# ADC.net
KiCad netlist of a schematic drawn in Altium Designer
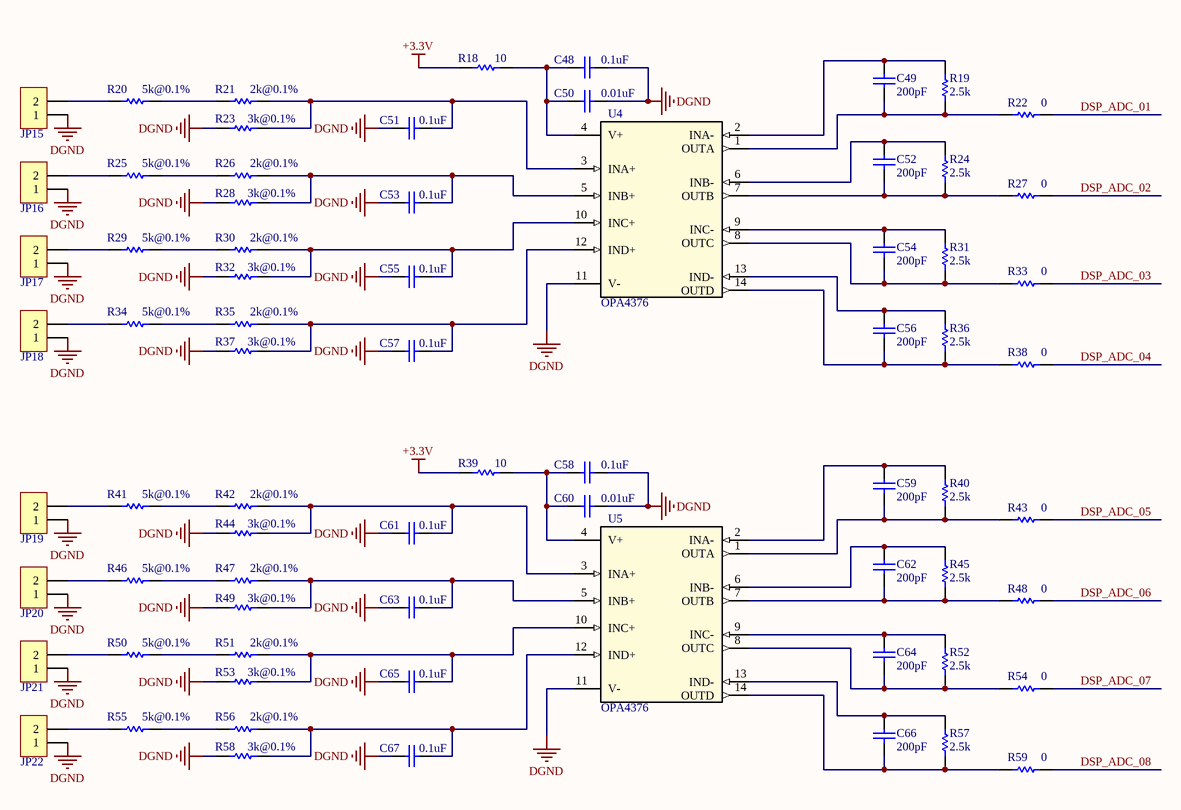
[diagram p0: ADC.SchDoc]

(export (version "E")
  (design (tool "Eeschema 10.0.6"))
  (components
    (comp (ref "C48")
      (value "0.1uF")
      (footprint "1608[0603]")
      (description "Capacitor")
      (fields (field (name "Comment") "Cap") (field (name "PUBLISHER") "Altium Limited"))
      (libsource (lib "Miscellaneous Devices") (part "Cap"))
    )
    (comp (ref "C49")
      (value "200pF")
      (footprint "1608[0603]")
      (description "Capacitor")
      (fields (field (name "Comment") "Cap") (field (name "PUBLISHER") "Altium Limited"))
      (libsource (lib "Miscellaneous Devices") (part "Cap"))
    )
    (comp (ref "C50")
      (value "0.01uF")
      (footprint "1608[0603]")
      (description "Capacitor")
      (fields (field (name "Comment") "Cap") (field (name "PUBLISHER") "Altium Limited"))
      (libsource (lib "Miscellaneous Devices") (part "Cap"))
    )
    (comp (ref "C51")
      (value "0.1uF")
      (footprint "1608[0603]")
      (description "Capacitor")
      (fields (field (name "Comment") "Cap") (field (name "PUBLISHER") "Altium Limited"))
      (libsource (lib "Miscellaneous Devices") (part "Cap"))
    )
    (comp (ref "C52")
      (value "200pF")
      (footprint "1608[0603]")
      (description "Capacitor")
      (fields (field (name "Comment") "Cap") (field (name "PUBLISHER") "Altium Limited"))
      (libsource (lib "Miscellaneous Devices") (part "Cap"))
    )
    (comp (ref "C53")
      (value "0.1uF")
      (footprint "1608[0603]")
      (description "Capacitor")
      (fields (field (name "Comment") "Cap") (field (name "PUBLISHER") "Altium Limited"))
      (libsource (lib "Miscellaneous Devices") (part "Cap"))
    )
    (comp (ref "C54")
      (value "200pF")
      (footprint "1608[0603]")
      (description "Capacitor")
      (fields (field (name "Comment") "Cap") (field (name "PUBLISHER") "Altium Limited"))
      (libsource (lib "Miscellaneous Devices") (part "Cap"))
    )
    (comp (ref "C55")
      (value "0.1uF")
      (footprint "1608[0603]")
      (description "Capacitor")
      (fields (field (name "Comment") "Cap") (field (name "PUBLISHER") "Altium Limited"))
      (libsource (lib "Miscellaneous Devices") (part "Cap"))
    )
    (comp (ref "C56")
      (value "200pF")
      (footprint "1608[0603]")
      (description "Capacitor")
      (fields (field (name "Comment") "Cap") (field (name "PUBLISHER") "Altium Limited"))
      (libsource (lib "Miscellaneous Devices") (part "Cap"))
    )
    (comp (ref "C57")
      (value "0.1uF")
      (footprint "1608[0603]")
      (description "Capacitor")
      (fields (field (name "Comment") "Cap") (field (name "PUBLISHER") "Altium Limited"))
      (libsource (lib "Miscellaneous Devices") (part "Cap"))
    )
    (comp (ref "C58")
      (value "0.1uF")
      (footprint "1608[0603]")
      (description "Capacitor")
      (fields (field (name "Comment") "Cap") (field (name "PUBLISHER") "Altium Limited"))
      (libsource (lib "Miscellaneous Devices") (part "Cap"))
    )
    (comp (ref "C59")
      (value "200pF")
      (footprint "1608[0603]")
      (description "Capacitor")
      (fields (field (name "Comment") "Cap") (field (name "PUBLISHER") "Altium Limited"))
      (libsource (lib "Miscellaneous Devices") (part "Cap"))
    )
    (comp (ref "C60")
      (value "0.01uF")
      (footprint "1608[0603]")
      (description "Capacitor")
      (fields (field (name "Comment") "Cap") (field (name "PUBLISHER") "Altium Limited"))
      (libsource (lib "Miscellaneous Devices") (part "Cap"))
    )
    (comp (ref "C61")
      (value "0.1uF")
      (footprint "1608[0603]")
      (description "Capacitor")
      (fields (field (name "Comment") "Cap") (field (name "PUBLISHER") "Altium Limited"))
      (libsource (lib "Miscellaneous Devices") (part "Cap"))
    )
    (comp (ref "C62")
      (value "200pF")
      (footprint "1608[0603]")
      (description "Capacitor")
      (fields (field (name "Comment") "Cap") (field (name "PUBLISHER") "Altium Limited"))
      (libsource (lib "Miscellaneous Devices") (part "Cap"))
    )
    (comp (ref "C63")
      (value "0.1uF")
      (footprint "1608[0603]")
      (description "Capacitor")
      (fields (field (name "Comment") "Cap") (field (name "PUBLISHER") "Altium Limited"))
      (libsource (lib "Miscellaneous Devices") (part "Cap"))
    )
    (comp (ref "C64")
      (value "200pF")
      (footprint "1608[0603]")
      (description "Capacitor")
      (fields (field (name "Comment") "Cap") (field (name "PUBLISHER") "Altium Limited"))
      (libsource (lib "Miscellaneous Devices") (part "Cap"))
    )
    (comp (ref "C65")
      (value "0.1uF")
      (footprint "1608[0603]")
      (description "Capacitor")
      (fields (field (name "Comment") "Cap") (field (name "PUBLISHER") "Altium Limited"))
      (libsource (lib "Miscellaneous Devices") (part "Cap"))
    )
    (comp (ref "C66")
      (value "200pF")
      (footprint "1608[0603]")
      (description "Capacitor")
      (fields (field (name "Comment") "Cap") (field (name "PUBLISHER") "Altium Limited"))
      (libsource (lib "Miscellaneous Devices") (part "Cap"))
    )
    (comp (ref "C67")
      (value "0.1uF")
      (footprint "1608[0603]")
      (description "Capacitor")
      (fields (field (name "Comment") "Cap") (field (name "PUBLISHER") "Altium Limited"))
      (libsource (lib "Miscellaneous Devices") (part "Cap"))
    )
    (comp (ref "JP15")
      (value "HDR-1X2")
      (footprint "MX 1.25-WI-2P")
      (description "2P接插件")
      (fields (field (name "版权归属") "源创客"))
      (libsource (lib "4.2   - 接插件-脚距1.25") (part "Header 2"))
    )
    (comp (ref "JP16")
      (value "HDR-1X2")
      (footprint "MX 1.25-WI-2P")
      (description "2P接插件")
      (fields (field (name "版权归属") "源创客"))
      (libsource (lib "4.2   - 接插件-脚距1.25") (part "Header 2"))
    )
    (comp (ref "JP17")
      (value "HDR-1X2")
      (footprint "MX 1.25-WI-2P")
      (description "2P接插件")
      (fields (field (name "版权归属") "源创客"))
      (libsource (lib "4.2   - 接插件-脚距1.25") (part "Header 2"))
    )
    (comp (ref "JP18")
      (value "HDR-1X2")
      (footprint "MX 1.25-WI-2P")
      (description "2P接插件")
      (fields (field (name "版权归属") "源创客"))
      (libsource (lib "4.2   - 接插件-脚距1.25") (part "Header 2"))
    )
    (comp (ref "JP19")
      (value "HDR-1X2")
      (footprint "MX 1.25-WI-2P")
      (description "2P接插件")
      (fields (field (name "版权归属") "源创客"))
      (libsource (lib "4.2   - 接插件-脚距1.25") (part "Header 2"))
    )
    (comp (ref "JP20")
      (value "HDR-1X2")
      (footprint "MX 1.25-WI-2P")
      (description "2P接插件")
      (fields (field (name "版权归属") "源创客"))
      (libsource (lib "4.2   - 接插件-脚距1.25") (part "Header 2"))
    )
    (comp (ref "JP21")
      (value "HDR-1X2")
      (footprint "MX 1.25-WI-2P")
      (description "2P接插件")
      (fields (field (name "版权归属") "源创客"))
      (libsource (lib "4.2   - 接插件-脚距1.25") (part "Header 2"))
    )
    (comp (ref "JP22")
      (value "HDR-1X2")
      (footprint "MX 1.25-WI-2P")
      (description "2P接插件")
      (fields (field (name "版权归属") "源创客"))
      (libsource (lib "4.2   - 接插件-脚距1.25") (part "Header 2"))
    )
    (comp (ref "R18")
      (value "10")
      (footprint "1608[0603]")
      (description "Resistor")
      (fields (field (name "Comment") "Res1") (field (name "PUBLISHER") "Altium Limited"))
      (libsource (lib "Miscellaneous Devices") (part "Res1"))
    )
    (comp (ref "R19")
      (value "2.5k")
      (footprint "1608[0603]")
      (description "Resistor")
      (fields (field (name "Comment") "Res1") (field (name "PUBLISHER") "Altium Limited"))
      (libsource (lib "Miscellaneous Devices") (part "Res1"))
    )
    (comp (ref "R20")
      (value "5k@0.1%")
      (footprint "1608[0603]")
      (description "Resistor")
      (fields (field (name "Comment") "Res1") (field (name "PUBLISHER") "Altium Limited"))
      (libsource (lib "Miscellaneous Devices") (part "Res1"))
    )
    (comp (ref "R21")
      (value "2k@0.1%")
      (footprint "1608[0603]")
      (description "Resistor")
      (fields (field (name "Comment") "Res1") (field (name "PUBLISHER") "Altium Limited"))
      (libsource (lib "Miscellaneous Devices") (part "Res1"))
    )
    (comp (ref "R22")
      (value "0")
      (footprint "1608[0603]")
      (description "Resistor")
      (fields (field (name "Comment") "Res1") (field (name "PUBLISHER") "Altium Limited"))
      (libsource (lib "Miscellaneous Devices") (part "Res1"))
    )
    (comp (ref "R23")
      (value "3k@0.1%")
      (footprint "1608[0603]")
      (description "Resistor")
      (fields (field (name "Comment") "Res1") (field (name "PUBLISHER") "Altium Limited"))
      (libsource (lib "Miscellaneous Devices") (part "Res1"))
    )
    (comp (ref "R24")
      (value "2.5k")
      (footprint "1608[0603]")
      (description "Resistor")
      (fields (field (name "Comment") "Res1") (field (name "PUBLISHER") "Altium Limited"))
      (libsource (lib "Miscellaneous Devices") (part "Res1"))
    )
    (comp (ref "R25")
      (value "5k@0.1%")
      (footprint "1608[0603]")
      (description "Resistor")
      (fields (field (name "Comment") "Res1") (field (name "PUBLISHER") "Altium Limited"))
      (libsource (lib "Miscellaneous Devices") (part "Res1"))
    )
    (comp (ref "R26")
      (value "2k@0.1%")
      (footprint "1608[0603]")
      (description "Resistor")
      (fields (field (name "Comment") "Res1") (field (name "PUBLISHER") "Altium Limited"))
      (libsource (lib "Miscellaneous Devices") (part "Res1"))
    )
    (comp (ref "R27")
      (value "0")
      (footprint "1608[0603]")
      (description "Resistor")
      (fields (field (name "Comment") "Res1") (field (name "PUBLISHER") "Altium Limited"))
      (libsource (lib "Miscellaneous Devices") (part "Res1"))
    )
    (comp (ref "R28")
      (value "3k@0.1%")
      (footprint "1608[0603]")
      (description "Resistor")
      (fields (field (name "Comment") "Res1") (field (name "PUBLISHER") "Altium Limited"))
      (libsource (lib "Miscellaneous Devices") (part "Res1"))
    )
    (comp (ref "R29")
      (value "5k@0.1%")
      (footprint "1608[0603]")
      (description "Resistor")
      (fields (field (name "Comment") "Res1") (field (name "PUBLISHER") "Altium Limited"))
      (libsource (lib "Miscellaneous Devices") (part "Res1"))
    )
    (comp (ref "R30")
      (value "2k@0.1%")
      (footprint "1608[0603]")
      (description "Resistor")
      (fields (field (name "Comment") "Res1") (field (name "PUBLISHER") "Altium Limited"))
      (libsource (lib "Miscellaneous Devices") (part "Res1"))
    )
    (comp (ref "R31")
      (value "2.5k")
      (footprint "1608[0603]")
      (description "Resistor")
      (fields (field (name "Comment") "Res1") (field (name "PUBLISHER") "Altium Limited"))
      (libsource (lib "Miscellaneous Devices") (part "Res1"))
    )
    (comp (ref "R32")
      (value "3k@0.1%")
      (footprint "1608[0603]")
      (description "Resistor")
      (fields (field (name "Comment") "Res1") (field (name "PUBLISHER") "Altium Limited"))
      (libsource (lib "Miscellaneous Devices") (part "Res1"))
    )
    (comp (ref "R33")
      (value "0")
      (footprint "1608[0603]")
      (description "Resistor")
      (fields (field (name "Comment") "Res1") (field (name "PUBLISHER") "Altium Limited"))
      (libsource (lib "Miscellaneous Devices") (part "Res1"))
    )
    (comp (ref "R34")
      (value "5k@0.1%")
      (footprint "1608[0603]")
      (description "Resistor")
      (fields (field (name "Comment") "Res1") (field (name "PUBLISHER") "Altium Limited"))
      (libsource (lib "Miscellaneous Devices") (part "Res1"))
    )
    (comp (ref "R35")
      (value "2k@0.1%")
      (footprint "1608[0603]")
      (description "Resistor")
      (fields (field (name "Comment") "Res1") (field (name "PUBLISHER") "Altium Limited"))
      (libsource (lib "Miscellaneous Devices") (part "Res1"))
    )
    (comp (ref "R36")
      (value "2.5k")
      (footprint "1608[0603]")
      (description "Resistor")
      (fields (field (name "Comment") "Res1") (field (name "PUBLISHER") "Altium Limited"))
      (libsource (lib "Miscellaneous Devices") (part "Res1"))
    )
    (comp (ref "R37")
      (value "3k@0.1%")
      (footprint "1608[0603]")
      (description "Resistor")
      (fields (field (name "Comment") "Res1") (field (name "PUBLISHER") "Altium Limited"))
      (libsource (lib "Miscellaneous Devices") (part "Res1"))
    )
    (comp (ref "R38")
      (value "0")
      (footprint "1608[0603]")
      (description "Resistor")
      (fields (field (name "Comment") "Res1") (field (name "PUBLISHER") "Altium Limited"))
      (libsource (lib "Miscellaneous Devices") (part "Res1"))
    )
    (comp (ref "R39")
      (value "10")
      (footprint "1608[0603]")
      (description "Resistor")
      (fields (field (name "Comment") "Res1") (field (name "PUBLISHER") "Altium Limited"))
      (libsource (lib "Miscellaneous Devices") (part "Res1"))
    )
    (comp (ref "R40")
      (value "2.5k")
      (footprint "1608[0603]")
      (description "Resistor")
      (fields (field (name "Comment") "Res1") (field (name "PUBLISHER") "Altium Limited"))
      (libsource (lib "Miscellaneous Devices") (part "Res1"))
    )
    (comp (ref "R41")
      (value "5k@0.1%")
      (footprint "1608[0603]")
      (description "Resistor")
      (fields (field (name "Comment") "Res1") (field (name "PUBLISHER") "Altium Limited"))
      (libsource (lib "Miscellaneous Devices") (part "Res1"))
    )
    (comp (ref "R42")
      (value "2k@0.1%")
      (footprint "1608[0603]")
      (description "Resistor")
      (fields (field (name "Comment") "Res1") (field (name "PUBLISHER") "Altium Limited"))
      (libsource (lib "Miscellaneous Devices") (part "Res1"))
    )
    (comp (ref "R43")
      (value "0")
      (footprint "1608[0603]")
      (description "Resistor")
      (fields (field (name "Comment") "Res1") (field (name "PUBLISHER") "Altium Limited"))
      (libsource (lib "Miscellaneous Devices") (part "Res1"))
    )
    (comp (ref "R44")
      (value "3k@0.1%")
      (footprint "1608[0603]")
      (description "Resistor")
      (fields (field (name "Comment") "Res1") (field (name "PUBLISHER") "Altium Limited"))
      (libsource (lib "Miscellaneous Devices") (part "Res1"))
    )
    (comp (ref "R45")
      (value "2.5k")
      (footprint "1608[0603]")
      (description "Resistor")
      (fields (field (name "Comment") "Res1") (field (name "PUBLISHER") "Altium Limited"))
      (libsource (lib "Miscellaneous Devices") (part "Res1"))
    )
    (comp (ref "R46")
      (value "5k@0.1%")
      (footprint "1608[0603]")
      (description "Resistor")
      (fields (field (name "Comment") "Res1") (field (name "PUBLISHER") "Altium Limited"))
      (libsource (lib "Miscellaneous Devices") (part "Res1"))
    )
    (comp (ref "R47")
      (value "2k@0.1%")
      (footprint "1608[0603]")
      (description "Resistor")
      (fields (field (name "Comment") "Res1") (field (name "PUBLISHER") "Altium Limited"))
      (libsource (lib "Miscellaneous Devices") (part "Res1"))
    )
    (comp (ref "R48")
      (value "0")
      (footprint "1608[0603]")
      (description "Resistor")
      (fields (field (name "Comment") "Res1") (field (name "PUBLISHER") "Altium Limited"))
      (libsource (lib "Miscellaneous Devices") (part "Res1"))
    )
    (comp (ref "R49")
      (value "3k@0.1%")
      (footprint "1608[0603]")
      (description "Resistor")
      (fields (field (name "Comment") "Res1") (field (name "PUBLISHER") "Altium Limited"))
      (libsource (lib "Miscellaneous Devices") (part "Res1"))
    )
    (comp (ref "R50")
      (value "5k@0.1%")
      (footprint "1608[0603]")
      (description "Resistor")
      (fields (field (name "Comment") "Res1") (field (name "PUBLISHER") "Altium Limited"))
      (libsource (lib "Miscellaneous Devices") (part "Res1"))
    )
    (comp (ref "R51")
      (value "2k@0.1%")
      (footprint "1608[0603]")
      (description "Resistor")
      (fields (field (name "Comment") "Res1") (field (name "PUBLISHER") "Altium Limited"))
      (libsource (lib "Miscellaneous Devices") (part "Res1"))
    )
    (comp (ref "R52")
      (value "2.5k")
      (footprint "1608[0603]")
      (description "Resistor")
      (fields (field (name "Comment") "Res1") (field (name "PUBLISHER") "Altium Limited"))
      (libsource (lib "Miscellaneous Devices") (part "Res1"))
    )
    (comp (ref "R53")
      (value "3k@0.1%")
      (footprint "1608[0603]")
      (description "Resistor")
      (fields (field (name "Comment") "Res1") (field (name "PUBLISHER") "Altium Limited"))
      (libsource (lib "Miscellaneous Devices") (part "Res1"))
    )
    (comp (ref "R54")
      (value "0")
      (footprint "1608[0603]")
      (description "Resistor")
      (fields (field (name "Comment") "Res1") (field (name "PUBLISHER") "Altium Limited"))
      (libsource (lib "Miscellaneous Devices") (part "Res1"))
    )
    (comp (ref "R55")
      (value "5k@0.1%")
      (footprint "1608[0603]")
      (description "Resistor")
      (fields (field (name "Comment") "Res1") (field (name "PUBLISHER") "Altium Limited"))
      (libsource (lib "Miscellaneous Devices") (part "Res1"))
    )
    (comp (ref "R56")
      (value "2k@0.1%")
      (footprint "1608[0603]")
      (description "Resistor")
      (fields (field (name "Comment") "Res1") (field (name "PUBLISHER") "Altium Limited"))
      (libsource (lib "Miscellaneous Devices") (part "Res1"))
    )
    (comp (ref "R57")
      (value "2.5k")
      (footprint "1608[0603]")
      (description "Resistor")
      (fields (field (name "Comment") "Res1") (field (name "PUBLISHER") "Altium Limited"))
      (libsource (lib "Miscellaneous Devices") (part "Res1"))
    )
    (comp (ref "R58")
      (value "3k@0.1%")
      (footprint "1608[0603]")
      (description "Resistor")
      (fields (field (name "Comment") "Res1") (field (name "PUBLISHER") "Altium Limited"))
      (libsource (lib "Miscellaneous Devices") (part "Res1"))
    )
    (comp (ref "R59")
      (value "0")
      (footprint "1608[0603]")
      (description "Resistor")
      (fields (field (name "Comment") "Res1") (field (name "PUBLISHER") "Altium Limited"))
      (libsource (lib "Miscellaneous Devices") (part "Res1"))
    )
    (comp (ref "U4")
      (value "OPA4376")
      (footprint "OPA4376_TSSOP")
      (fields
        (field (name "MANUFACTURER") "Texas Instruments")
        (field (name "MANUFACTURER_PART_NUMBER") "opa4376_pw_14")
      )
      (libsource (lib "DSP_FPGA_Lib") (part "OPA4376"))
    )
    (comp (ref "U5")
      (value "OPA4376")
      (footprint "OPA4376_TSSOP")
      (fields
        (field (name "MANUFACTURER") "Texas Instruments")
        (field (name "MANUFACTURER_PART_NUMBER") "opa4376_pw_14")
      )
      (libsource (lib "DSP_FPGA_Lib") (part "OPA4376"))
    )
  )
  (nets
    (net (code "1") (name "+3.3V") (class "Default")
      (node (ref "R18") (pin "2") (pinfunction "2_2") (pintype "passive"))
      (node (ref "R39") (pin "2") (pinfunction "2_2") (pintype "passive"))
    )
    (net (code "2") (name "/DSP_ADC_01") (class "Default")
      (node (ref "R22") (pin "2") (pinfunction "2_2") (pintype "passive"))
    )
    (net (code "3") (name "/DSP_ADC_02") (class "Default")
      (node (ref "R27") (pin "2") (pinfunction "2_2") (pintype "passive"))
    )
    (net (code "4") (name "/DSP_ADC_03") (class "Default")
      (node (ref "R33") (pin "2") (pinfunction "2_2") (pintype "passive"))
    )
    (net (code "5") (name "/DSP_ADC_04") (class "Default")
      (node (ref "R38") (pin "2") (pinfunction "2_2") (pintype "passive"))
    )
    (net (code "6") (name "/DSP_ADC_05") (class "Default")
      (node (ref "R43") (pin "2") (pinfunction "2_2") (pintype "passive"))
    )
    (net (code "7") (name "/DSP_ADC_06") (class "Default")
      (node (ref "R48") (pin "2") (pinfunction "2_2") (pintype "passive"))
    )
    (net (code "8") (name "/DSP_ADC_07") (class "Default")
      (node (ref "R54") (pin "2") (pinfunction "2_2") (pintype "passive"))
    )
    (net (code "9") (name "/DSP_ADC_08") (class "Default")
      (node (ref "R59") (pin "2") (pinfunction "2_2") (pintype "passive"))
    )
    (net (code "10") (name "DGND") (class "Default")
      (node (ref "C48") (pin "2") (pinfunction "2_2") (pintype "passive"))
      (node (ref "C50") (pin "2") (pinfunction "2_2") (pintype "passive"))
      (node (ref "C51") (pin "1") (pinfunction "1_1") (pintype "passive"))
      (node (ref "C53") (pin "1") (pinfunction "1_1") (pintype "passive"))
      (node (ref "C55") (pin "1") (pinfunction "1_1") (pintype "passive"))
      (node (ref "C57") (pin "1") (pinfunction "1_1") (pintype "passive"))
      (node (ref "C58") (pin "2") (pinfunction "2_2") (pintype "passive"))
      (node (ref "C60") (pin "2") (pinfunction "2_2") (pintype "passive"))
      (node (ref "C61") (pin "1") (pinfunction "1_1") (pintype "passive"))
      (node (ref "C63") (pin "1") (pinfunction "1_1") (pintype "passive"))
      (node (ref "C65") (pin "1") (pinfunction "1_1") (pintype "passive"))
      (node (ref "C67") (pin "1") (pinfunction "1_1") (pintype "passive"))
      (node (ref "JP15") (pin "1") (pinfunction "1_1") (pintype "passive"))
      (node (ref "JP16") (pin "1") (pinfunction "1_1") (pintype "passive"))
      (node (ref "JP17") (pin "1") (pinfunction "1_1") (pintype "passive"))
      (node (ref "JP18") (pin "1") (pinfunction "1_1") (pintype "passive"))
      (node (ref "JP19") (pin "1") (pinfunction "1_1") (pintype "passive"))
      (node (ref "JP20") (pin "1") (pinfunction "1_1") (pintype "passive"))
      (node (ref "JP21") (pin "1") (pinfunction "1_1") (pintype "passive"))
      (node (ref "JP22") (pin "1") (pinfunction "1_1") (pintype "passive"))
      (node (ref "R23") (pin "2") (pinfunction "2_2") (pintype "passive"))
      (node (ref "R28") (pin "2") (pinfunction "2_2") (pintype "passive"))
      (node (ref "R32") (pin "2") (pinfunction "2_2") (pintype "passive"))
      (node (ref "R37") (pin "2") (pinfunction "2_2") (pintype "passive"))
      (node (ref "R44") (pin "2") (pinfunction "2_2") (pintype "passive"))
      (node (ref "R49") (pin "2") (pinfunction "2_2") (pintype "passive"))
      (node (ref "R53") (pin "2") (pinfunction "2_2") (pintype "passive"))
      (node (ref "R58") (pin "2") (pinfunction "2_2") (pintype "passive"))
      (node (ref "U4") (pin "11") (pinfunction "V-_11") (pintype "power_in"))
      (node (ref "U5") (pin "11") (pinfunction "V-_11") (pintype "power_in"))
    )
    (net (code "11") (name "Net-(JP15-Pad2)") (class "Default")
      (node (ref "JP15") (pin "2") (pinfunction "2_2") (pintype "passive"))
      (node (ref "R20") (pin "2") (pinfunction "2_2") (pintype "passive"))
    )
    (net (code "12") (name "Net-(JP16-Pad2)") (class "Default")
      (node (ref "JP16") (pin "2") (pinfunction "2_2") (pintype "passive"))
      (node (ref "R25") (pin "2") (pinfunction "2_2") (pintype "passive"))
    )
    (net (code "13") (name "Net-(JP17-Pad2)") (class "Default")
      (node (ref "JP17") (pin "2") (pinfunction "2_2") (pintype "passive"))
      (node (ref "R29") (pin "2") (pinfunction "2_2") (pintype "passive"))
    )
    (net (code "14") (name "Net-(JP18-Pad2)") (class "Default")
      (node (ref "JP18") (pin "2") (pinfunction "2_2") (pintype "passive"))
      (node (ref "R34") (pin "2") (pinfunction "2_2") (pintype "passive"))
    )
    (net (code "15") (name "Net-(JP19-Pad2)") (class "Default")
      (node (ref "JP19") (pin "2") (pinfunction "2_2") (pintype "passive"))
      (node (ref "R41") (pin "2") (pinfunction "2_2") (pintype "passive"))
    )
    (net (code "16") (name "Net-(JP20-Pad2)") (class "Default")
      (node (ref "JP20") (pin "2") (pinfunction "2_2") (pintype "passive"))
      (node (ref "R46") (pin "2") (pinfunction "2_2") (pintype "passive"))
    )
    (net (code "17") (name "Net-(JP21-Pad2)") (class "Default")
      (node (ref "JP21") (pin "2") (pinfunction "2_2") (pintype "passive"))
      (node (ref "R50") (pin "2") (pinfunction "2_2") (pintype "passive"))
    )
    (net (code "18") (name "Net-(JP22-Pad2)") (class "Default")
      (node (ref "JP22") (pin "2") (pinfunction "2_2") (pintype "passive"))
      (node (ref "R55") (pin "2") (pinfunction "2_2") (pintype "passive"))
    )
    (net (code "19") (name "Net-(R20-Pad1)") (class "Default")
      (node (ref "R20") (pin "1") (pinfunction "1_1") (pintype "passive"))
      (node (ref "R21") (pin "2") (pinfunction "2_2") (pintype "passive"))
    )
    (net (code "20") (name "Net-(R25-Pad1)") (class "Default")
      (node (ref "R25") (pin "1") (pinfunction "1_1") (pintype "passive"))
      (node (ref "R26") (pin "2") (pinfunction "2_2") (pintype "passive"))
    )
    (net (code "21") (name "Net-(R29-Pad1)") (class "Default")
      (node (ref "R29") (pin "1") (pinfunction "1_1") (pintype "passive"))
      (node (ref "R30") (pin "2") (pinfunction "2_2") (pintype "passive"))
    )
    (net (code "22") (name "Net-(R34-Pad1)") (class "Default")
      (node (ref "R34") (pin "1") (pinfunction "1_1") (pintype "passive"))
      (node (ref "R35") (pin "2") (pinfunction "2_2") (pintype "passive"))
    )
    (net (code "23") (name "Net-(R41-Pad1)") (class "Default")
      (node (ref "R41") (pin "1") (pinfunction "1_1") (pintype "passive"))
      (node (ref "R42") (pin "2") (pinfunction "2_2") (pintype "passive"))
    )
    (net (code "24") (name "Net-(R46-Pad1)") (class "Default")
      (node (ref "R46") (pin "1") (pinfunction "1_1") (pintype "passive"))
      (node (ref "R47") (pin "2") (pinfunction "2_2") (pintype "passive"))
    )
    (net (code "25") (name "Net-(R50-Pad1)") (class "Default")
      (node (ref "R50") (pin "1") (pinfunction "1_1") (pintype "passive"))
      (node (ref "R51") (pin "2") (pinfunction "2_2") (pintype "passive"))
    )
    (net (code "26") (name "Net-(R55-Pad1)") (class "Default")
      (node (ref "R55") (pin "1") (pinfunction "1_1") (pintype "passive"))
      (node (ref "R56") (pin "2") (pinfunction "2_2") (pintype "passive"))
    )
    (net (code "27") (name "Net-(U4-INA+)") (class "Default")
      (node (ref "C51") (pin "2") (pinfunction "2_2") (pintype "passive"))
      (node (ref "R21") (pin "1") (pinfunction "1_1") (pintype "passive"))
      (node (ref "R23") (pin "1") (pinfunction "1_1") (pintype "passive"))
      (node (ref "U4") (pin "3") (pinfunction "INA+_3") (pintype "input"))
    )
    (net (code "28") (name "Net-(U4-INA-)") (class "Default")
      (node (ref "C49") (pin "1") (pinfunction "1_1") (pintype "passive"))
      (node (ref "R19") (pin "2") (pinfunction "2_2") (pintype "passive"))
      (node (ref "U4") (pin "2") (pinfunction "INA-_2") (pintype "input"))
    )
    (net (code "29") (name "Net-(U4-INB+)") (class "Default")
      (node (ref "C53") (pin "2") (pinfunction "2_2") (pintype "passive"))
      (node (ref "R26") (pin "1") (pinfunction "1_1") (pintype "passive"))
      (node (ref "R28") (pin "1") (pinfunction "1_1") (pintype "passive"))
      (node (ref "U4") (pin "5") (pinfunction "INB+_5") (pintype "input"))
    )
    (net (code "30") (name "Net-(U4-INB-)") (class "Default")
      (node (ref "C52") (pin "1") (pinfunction "1_1") (pintype "passive"))
      (node (ref "R24") (pin "2") (pinfunction "2_2") (pintype "passive"))
      (node (ref "U4") (pin "6") (pinfunction "INB-_6") (pintype "input"))
    )
    (net (code "31") (name "Net-(U4-INC+)") (class "Default")
      (node (ref "C55") (pin "2") (pinfunction "2_2") (pintype "passive"))
      (node (ref "R30") (pin "1") (pinfunction "1_1") (pintype "passive"))
      (node (ref "R32") (pin "1") (pinfunction "1_1") (pintype "passive"))
      (node (ref "U4") (pin "10") (pinfunction "INC+_10") (pintype "input"))
    )
    (net (code "32") (name "Net-(U4-INC-)") (class "Default")
      (node (ref "C54") (pin "1") (pinfunction "1_1") (pintype "passive"))
      (node (ref "R31") (pin "2") (pinfunction "2_2") (pintype "passive"))
      (node (ref "U4") (pin "9") (pinfunction "INC-_9") (pintype "input"))
    )
    (net (code "33") (name "Net-(U4-IND+)") (class "Default")
      (node (ref "C57") (pin "2") (pinfunction "2_2") (pintype "passive"))
      (node (ref "R35") (pin "1") (pinfunction "1_1") (pintype "passive"))
      (node (ref "R37") (pin "1") (pinfunction "1_1") (pintype "passive"))
      (node (ref "U4") (pin "12") (pinfunction "IND+_12") (pintype "input"))
    )
    (net (code "34") (name "Net-(U4-IND-)") (class "Default")
      (node (ref "C56") (pin "1") (pinfunction "1_1") (pintype "passive"))
      (node (ref "R36") (pin "2") (pinfunction "2_2") (pintype "passive"))
      (node (ref "U4") (pin "13") (pinfunction "IND-_13") (pintype "input"))
    )
    (net (code "35") (name "Net-(U4-OUTA)") (class "Default")
      (node (ref "C49") (pin "2") (pinfunction "2_2") (pintype "passive"))
      (node (ref "R19") (pin "1") (pinfunction "1_1") (pintype "passive"))
      (node (ref "R22") (pin "1") (pinfunction "1_1") (pintype "passive"))
      (node (ref "U4") (pin "1") (pinfunction "OUTA_1") (pintype "output"))
    )
    (net (code "36") (name "Net-(U4-OUTB)") (class "Default")
      (node (ref "C52") (pin "2") (pinfunction "2_2") (pintype "passive"))
      (node (ref "R24") (pin "1") (pinfunction "1_1") (pintype "passive"))
      (node (ref "R27") (pin "1") (pinfunction "1_1") (pintype "passive"))
      (node (ref "U4") (pin "7") (pinfunction "OUTB_7") (pintype "output"))
    )
    (net (code "37") (name "Net-(U4-OUTC)") (class "Default")
      (node (ref "C54") (pin "2") (pinfunction "2_2") (pintype "passive"))
      (node (ref "R31") (pin "1") (pinfunction "1_1") (pintype "passive"))
      (node (ref "R33") (pin "1") (pinfunction "1_1") (pintype "passive"))
      (node (ref "U4") (pin "8") (pinfunction "OUTC_8") (pintype "output"))
    )
    (net (code "38") (name "Net-(U4-OUTD)") (class "Default")
      (node (ref "C56") (pin "2") (pinfunction "2_2") (pintype "passive"))
      (node (ref "R36") (pin "1") (pinfunction "1_1") (pintype "passive"))
      (node (ref "R38") (pin "1") (pinfunction "1_1") (pintype "passive"))
      (node (ref "U4") (pin "14") (pinfunction "OUTD_14") (pintype "output"))
    )
    (net (code "39") (name "Net-(U4-V+)") (class "Default")
      (node (ref "C48") (pin "1") (pinfunction "1_1") (pintype "passive"))
      (node (ref "C50") (pin "1") (pinfunction "1_1") (pintype "passive"))
      (node (ref "R18") (pin "1") (pinfunction "1_1") (pintype "passive"))
      (node (ref "U4") (pin "4") (pinfunction "V+_4") (pintype "power_in"))
    )
    (net (code "40") (name "Net-(U5-INA+)") (class "Default")
      (node (ref "C61") (pin "2") (pinfunction "2_2") (pintype "passive"))
      (node (ref "R42") (pin "1") (pinfunction "1_1") (pintype "passive"))
      (node (ref "R44") (pin "1") (pinfunction "1_1") (pintype "passive"))
      (node (ref "U5") (pin "3") (pinfunction "INA+_3") (pintype "input"))
    )
    (net (code "41") (name "Net-(U5-INA-)") (class "Default")
      (node (ref "C59") (pin "1") (pinfunction "1_1") (pintype "passive"))
      (node (ref "R40") (pin "2") (pinfunction "2_2") (pintype "passive"))
      (node (ref "U5") (pin "2") (pinfunction "INA-_2") (pintype "input"))
    )
    (net (code "42") (name "Net-(U5-INB+)") (class "Default")
      (node (ref "C63") (pin "2") (pinfunction "2_2") (pintype "passive"))
      (node (ref "R47") (pin "1") (pinfunction "1_1") (pintype "passive"))
      (node (ref "R49") (pin "1") (pinfunction "1_1") (pintype "passive"))
      (node (ref "U5") (pin "5") (pinfunction "INB+_5") (pintype "input"))
    )
    (net (code "43") (name "Net-(U5-INB-)") (class "Default")
      (node (ref "C62") (pin "1") (pinfunction "1_1") (pintype "passive"))
      (node (ref "R45") (pin "2") (pinfunction "2_2") (pintype "passive"))
      (node (ref "U5") (pin "6") (pinfunction "INB-_6") (pintype "input"))
    )
    (net (code "44") (name "Net-(U5-INC+)") (class "Default")
      (node (ref "C65") (pin "2") (pinfunction "2_2") (pintype "passive"))
      (node (ref "R51") (pin "1") (pinfunction "1_1") (pintype "passive"))
      (node (ref "R53") (pin "1") (pinfunction "1_1") (pintype "passive"))
      (node (ref "U5") (pin "10") (pinfunction "INC+_10") (pintype "input"))
    )
    (net (code "45") (name "Net-(U5-INC-)") (class "Default")
      (node (ref "C64") (pin "1") (pinfunction "1_1") (pintype "passive"))
      (node (ref "R52") (pin "2") (pinfunction "2_2") (pintype "passive"))
      (node (ref "U5") (pin "9") (pinfunction "INC-_9") (pintype "input"))
    )
    (net (code "46") (name "Net-(U5-IND+)") (class "Default")
      (node (ref "C67") (pin "2") (pinfunction "2_2") (pintype "passive"))
      (node (ref "R56") (pin "1") (pinfunction "1_1") (pintype "passive"))
      (node (ref "R58") (pin "1") (pinfunction "1_1") (pintype "passive"))
      (node (ref "U5") (pin "12") (pinfunction "IND+_12") (pintype "input"))
    )
    (net (code "47") (name "Net-(U5-IND-)") (class "Default")
      (node (ref "C66") (pin "1") (pinfunction "1_1") (pintype "passive"))
      (node (ref "R57") (pin "2") (pinfunction "2_2") (pintype "passive"))
      (node (ref "U5") (pin "13") (pinfunction "IND-_13") (pintype "input"))
    )
    (net (code "48") (name "Net-(U5-OUTA)") (class "Default")
      (node (ref "C59") (pin "2") (pinfunction "2_2") (pintype "passive"))
      (node (ref "R40") (pin "1") (pinfunction "1_1") (pintype "passive"))
      (node (ref "R43") (pin "1") (pinfunction "1_1") (pintype "passive"))
      (node (ref "U5") (pin "1") (pinfunction "OUTA_1") (pintype "output"))
    )
    (net (code "49") (name "Net-(U5-OUTB)") (class "Default")
      (node (ref "C62") (pin "2") (pinfunction "2_2") (pintype "passive"))
      (node (ref "R45") (pin "1") (pinfunction "1_1") (pintype "passive"))
      (node (ref "R48") (pin "1") (pinfunction "1_1") (pintype "passive"))
      (node (ref "U5") (pin "7") (pinfunction "OUTB_7") (pintype "output"))
    )
    (net (code "50") (name "Net-(U5-OUTC)") (class "Default")
      (node (ref "C64") (pin "2") (pinfunction "2_2") (pintype "passive"))
      (node (ref "R52") (pin "1") (pinfunction "1_1") (pintype "passive"))
      (node (ref "R54") (pin "1") (pinfunction "1_1") (pintype "passive"))
      (node (ref "U5") (pin "8") (pinfunction "OUTC_8") (pintype "output"))
    )
    (net (code "51") (name "Net-(U5-OUTD)") (class "Default")
      (node (ref "C66") (pin "2") (pinfunction "2_2") (pintype "passive"))
      (node (ref "R57") (pin "1") (pinfunction "1_1") (pintype "passive"))
      (node (ref "R59") (pin "1") (pinfunction "1_1") (pintype "passive"))
      (node (ref "U5") (pin "14") (pinfunction "OUTD_14") (pintype "output"))
    )
    (net (code "52") (name "Net-(U5-V+)") (class "Default")
      (node (ref "C58") (pin "1") (pinfunction "1_1") (pintype "passive"))
      (node (ref "C60") (pin "1") (pinfunction "1_1") (pintype "passive"))
      (node (ref "R39") (pin "1") (pinfunction "1_1") (pintype "passive"))
      (node (ref "U5") (pin "4") (pinfunction "V+_4") (pintype "power_in"))
    )
  )
)
